# buck_module_5v.net
KiCad netlist of a schematic drawn in EAGLE
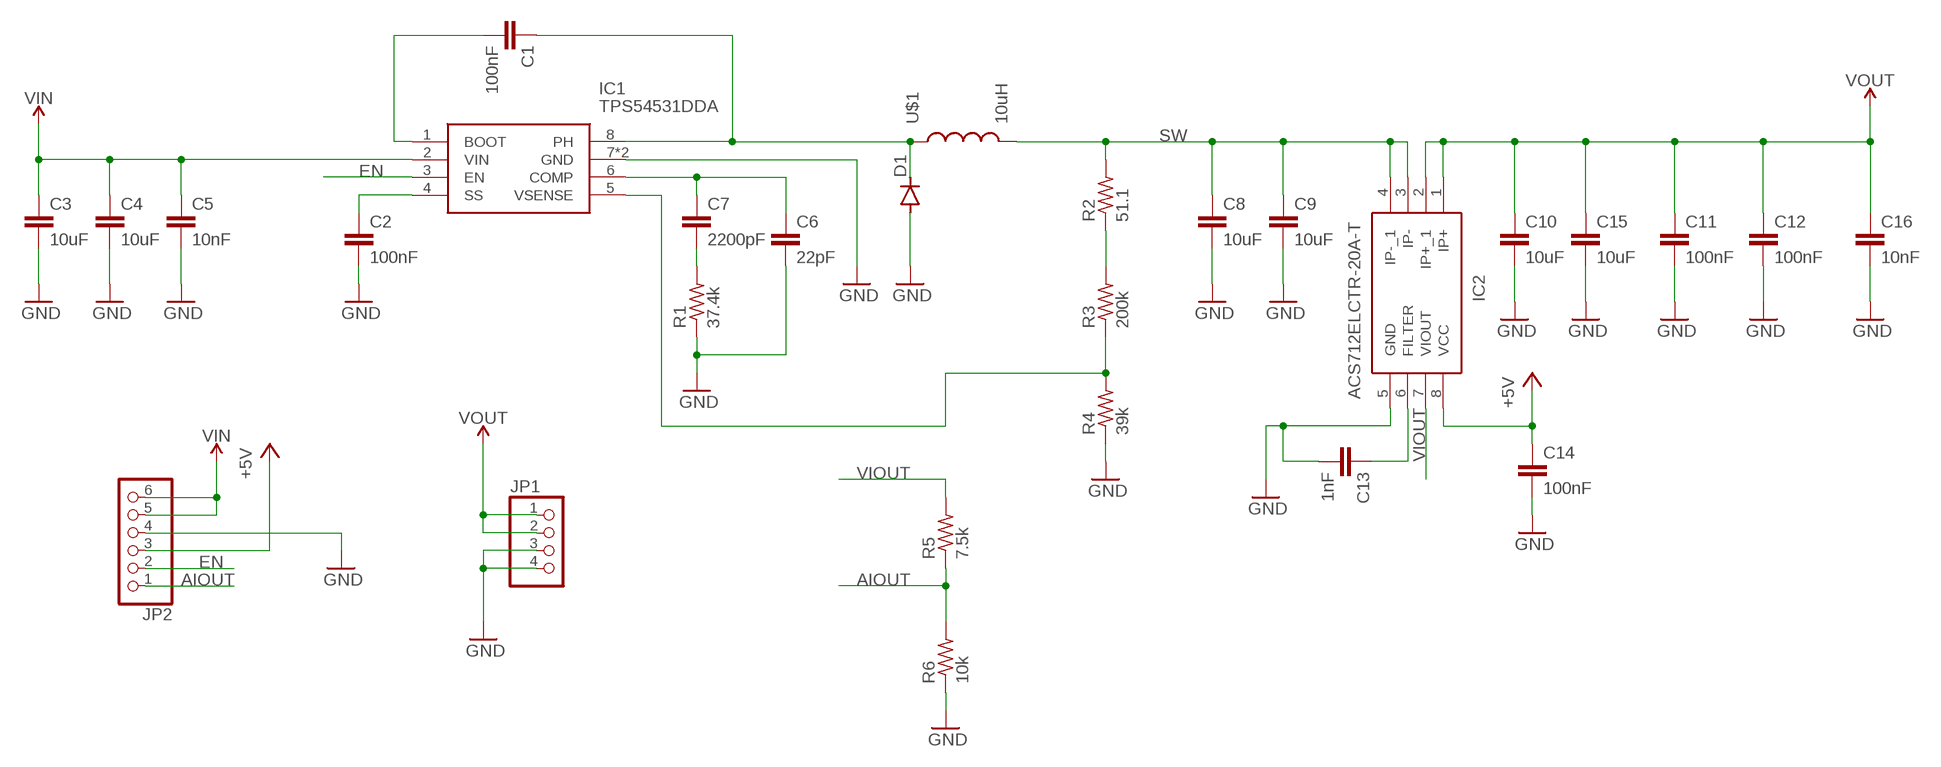
[diagram p0: schematic, sheet 1]

(export (version "E")
  (design (tool "Eeschema 10.0.6"))
  (components
    (comp (ref "C1")
      (value "100nF")
      (footprint "eagle-import:C0603")
      (libsource (lib "eagle-import") (part "C-EUC0603"))
    )
    (comp (ref "C2")
      (value "100nF")
      (footprint "eagle-import:C0603")
      (libsource (lib "eagle-import") (part "C-EUC0603"))
    )
    (comp (ref "C3")
      (value "10uF")
      (footprint "eagle-import:C1206")
      (libsource (lib "eagle-import") (part "C-EUC1206"))
    )
    (comp (ref "C4")
      (value "10uF")
      (footprint "eagle-import:C1206")
      (libsource (lib "eagle-import") (part "C-EUC1206"))
    )
    (comp (ref "C5")
      (value "10nF")
      (footprint "eagle-import:C0603")
      (libsource (lib "eagle-import") (part "C-EUC0603"))
    )
    (comp (ref "C6")
      (value "22pF")
      (footprint "eagle-import:C0603")
      (libsource (lib "eagle-import") (part "C-EUC0603"))
    )
    (comp (ref "C7")
      (value "2200pF")
      (footprint "eagle-import:C0603")
      (libsource (lib "eagle-import") (part "C-EUC0603"))
    )
    (comp (ref "C8")
      (value "10uF")
      (footprint "eagle-import:C1206")
      (libsource (lib "eagle-import") (part "C-EUC1206"))
    )
    (comp (ref "C9")
      (value "10uF")
      (footprint "eagle-import:C1206")
      (libsource (lib "eagle-import") (part "C-EUC1206"))
    )
    (comp (ref "C10")
      (value "10uF")
      (footprint "eagle-import:C1206")
      (libsource (lib "eagle-import") (part "C-EUC1206"))
    )
    (comp (ref "C11")
      (value "100nF")
      (footprint "eagle-import:C0603")
      (libsource (lib "eagle-import") (part "C-EUC0603"))
    )
    (comp (ref "C12")
      (value "100nF")
      (footprint "eagle-import:C0603")
      (libsource (lib "eagle-import") (part "C-EUC0603"))
    )
    (comp (ref "C13")
      (value "1nF")
      (footprint "eagle-import:C0603")
      (libsource (lib "eagle-import") (part "C-EUC0603"))
    )
    (comp (ref "C14")
      (value "100nF")
      (footprint "eagle-import:C0603")
      (libsource (lib "eagle-import") (part "C-EUC0603"))
    )
    (comp (ref "C15")
      (value "10uF")
      (footprint "eagle-import:C1206")
      (libsource (lib "eagle-import") (part "C-EUC1206"))
    )
    (comp (ref "C16")
      (value "10nF")
      (footprint "eagle-import:C0603")
      (libsource (lib "eagle-import") (part "C-EUC0603"))
    )
    (comp (ref "D1")
      (value "DIODE-DO214AA")
      (footprint "eagle-import:DO214AA")
      (libsource (lib "eagle-import") (part "DIODE-DO214AA"))
    )
    (comp (ref "IC1")
      (value "TPS54531DDA")
      (footprint "eagle-import:SOIC127P600X170-9N")
      (fields (field (name "MOUSER_PART_NUMBER") "595-TPS54531DDA"))
      (libsource (lib "eagle-import") (part "TPS54531DDA"))
    )
    (comp (ref "IC2")
      (value "ACS712ELCTR-20A-T")
      (footprint "eagle-import:SOIC127P600X175-8N")
      (fields (field (name "RS_PART_NUMBER") "6807135P"))
      (libsource (lib "eagle-import") (part "ACS712ELCTR-20A-T"))
    )
    (comp (ref "JP1")
      (value "PINHD-1X4")
      (footprint "eagle-import:1X04")
      (libsource (lib "eagle-import") (part "PINHD-1X4"))
    )
    (comp (ref "JP2")
      (value "PINHD-1X6")
      (footprint "eagle-import:1X06")
      (libsource (lib "eagle-import") (part "PINHD-1X6"))
    )
    (comp (ref "R1")
      (value "37.4k")
      (footprint "eagle-import:R0603")
      (libsource (lib "eagle-import") (part "R-US_R0603"))
    )
    (comp (ref "R2")
      (value "51.1")
      (footprint "eagle-import:R0603")
      (libsource (lib "eagle-import") (part "R-US_R0603"))
    )
    (comp (ref "R3")
      (value "200k")
      (footprint "eagle-import:R0603")
      (libsource (lib "eagle-import") (part "R-US_R0603"))
    )
    (comp (ref "R4")
      (value "39k")
      (footprint "eagle-import:R0603")
      (libsource (lib "eagle-import") (part "R-US_R0603"))
    )
    (comp (ref "R5")
      (value "7.5k")
      (footprint "eagle-import:R0603")
      (libsource (lib "eagle-import") (part "R-US_R0603"))
    )
    (comp (ref "R6")
      (value "10k")
      (footprint "eagle-import:R0603")
      (libsource (lib "eagle-import") (part "R-US_R0603"))
    )
    (comp (ref "U$1")
      (value "10uH")
      (footprint "eagle-import:22UH-1040-5A")
      (libsource (lib "eagle-import") (part "22UH-1040-5A"))
    )
  )
  (nets
    (net (code "1") (name "+5V") (class "Default")
      (node (ref "C14") (pin "1") (pinfunction "1_1") (pintype "passive"))
      (node (ref "IC2") (pin "8") (pinfunction "VCC_8") (pintype "power_in"))
      (node (ref "JP2") (pin "3") (pinfunction "3_3") (pintype "passive"))
    )
    (net (code "2") (name "/AIOUT") (class "Default")
      (node (ref "JP2") (pin "1") (pinfunction "1_1") (pintype "passive"))
      (node (ref "R5") (pin "1") (pinfunction "1_1") (pintype "passive"))
      (node (ref "R6") (pin "2") (pinfunction "2_2") (pintype "passive"))
    )
    (net (code "3") (name "/EN") (class "Default")
      (node (ref "IC1") (pin "3") (pinfunction "EN_3") (pintype "bidirectional"))
      (node (ref "JP2") (pin "2") (pinfunction "2_2") (pintype "passive"))
    )
    (net (code "4") (name "/SW") (class "Default")
      (node (ref "C8") (pin "1") (pinfunction "1_1") (pintype "passive"))
      (node (ref "C9") (pin "1") (pinfunction "1_1") (pintype "passive"))
      (node (ref "IC2") (pin "3") (pinfunction "IP-_3") (pintype "bidirectional"))
      (node (ref "IC2") (pin "4") (pinfunction "IP-_1_4") (pintype "bidirectional"))
      (node (ref "R2") (pin "2") (pinfunction "2_2") (pintype "passive"))
      (node (ref "U$1") (pin "P$2") (pinfunction "2_P$2") (pintype "passive"))
    )
    (net (code "5") (name "/VIOUT") (class "Default")
      (node (ref "IC2") (pin "7") (pinfunction "VIOUT_7") (pintype "bidirectional"))
      (node (ref "R5") (pin "2") (pinfunction "2_2") (pintype "passive"))
    )
    (net (code "6") (name "GND") (class "Default")
      (node (ref "C10") (pin "2") (pinfunction "2_2") (pintype "passive"))
      (node (ref "C11") (pin "2") (pinfunction "2_2") (pintype "passive"))
      (node (ref "C12") (pin "2") (pinfunction "2_2") (pintype "passive"))
      (node (ref "C13") (pin "2") (pinfunction "2_2") (pintype "passive"))
      (node (ref "C14") (pin "2") (pinfunction "2_2") (pintype "passive"))
      (node (ref "C15") (pin "2") (pinfunction "2_2") (pintype "passive"))
      (node (ref "C16") (pin "2") (pinfunction "2_2") (pintype "passive"))
      (node (ref "C2") (pin "2") (pinfunction "2_2") (pintype "passive"))
      (node (ref "C3") (pin "2") (pinfunction "2_2") (pintype "passive"))
      (node (ref "C4") (pin "2") (pinfunction "2_2") (pintype "passive"))
      (node (ref "C5") (pin "2") (pinfunction "2_2") (pintype "passive"))
      (node (ref "C6") (pin "2") (pinfunction "2_2") (pintype "passive"))
      (node (ref "C8") (pin "2") (pinfunction "2_2") (pintype "passive"))
      (node (ref "C9") (pin "2") (pinfunction "2_2") (pintype "passive"))
      (node (ref "D1") (pin "A") (pinfunction "A_A") (pintype "passive"))
      (node (ref "IC1") (pin "7") (pinfunction "GND_7") (pintype "bidirectional"))
      (node (ref "IC1") (pin "9") (pinfunction "GND_9") (pintype "bidirectional"))
      (node (ref "IC2") (pin "5") (pinfunction "GND_5") (pintype "power_in"))
      (node (ref "JP1") (pin "3") (pinfunction "3_3") (pintype "passive"))
      (node (ref "JP1") (pin "4") (pinfunction "4_4") (pintype "passive"))
      (node (ref "JP2") (pin "4") (pinfunction "4_4") (pintype "passive"))
      (node (ref "R1") (pin "1") (pinfunction "1_1") (pintype "passive"))
      (node (ref "R4") (pin "1") (pinfunction "1_1") (pintype "passive"))
      (node (ref "R6") (pin "1") (pinfunction "1_1") (pintype "passive"))
    )
    (net (code "7") (name "Net-(C7-Pad2)") (class "Default")
      (node (ref "C7") (pin "2") (pinfunction "2_2") (pintype "passive"))
      (node (ref "R1") (pin "2") (pinfunction "2_2") (pintype "passive"))
    )
    (net (code "8") (name "Net-(IC1-BOOT)") (class "Default")
      (node (ref "C1") (pin "2") (pinfunction "2_2") (pintype "passive"))
      (node (ref "IC1") (pin "1") (pinfunction "BOOT_1") (pintype "bidirectional"))
    )
    (net (code "9") (name "Net-(IC1-COMP)") (class "Default")
      (node (ref "C6") (pin "1") (pinfunction "1_1") (pintype "passive"))
      (node (ref "C7") (pin "1") (pinfunction "1_1") (pintype "passive"))
      (node (ref "IC1") (pin "6") (pinfunction "COMP_6") (pintype "bidirectional"))
    )
    (net (code "10") (name "Net-(IC1-PH)") (class "Default")
      (node (ref "C1") (pin "1") (pinfunction "1_1") (pintype "passive"))
      (node (ref "D1") (pin "C") (pinfunction "C_C") (pintype "passive"))
      (node (ref "IC1") (pin "8") (pinfunction "PH_8") (pintype "bidirectional"))
      (node (ref "U$1") (pin "P$1") (pinfunction "1_P$1") (pintype "passive"))
    )
    (net (code "11") (name "Net-(IC1-SS)") (class "Default")
      (node (ref "C2") (pin "1") (pinfunction "1_1") (pintype "passive"))
      (node (ref "IC1") (pin "4") (pinfunction "SS_4") (pintype "bidirectional"))
    )
    (net (code "12") (name "Net-(IC1-VSENSE)") (class "Default")
      (node (ref "IC1") (pin "5") (pinfunction "VSENSE_5") (pintype "bidirectional"))
      (node (ref "R3") (pin "1") (pinfunction "1_1") (pintype "passive"))
      (node (ref "R4") (pin "2") (pinfunction "2_2") (pintype "passive"))
    )
    (net (code "13") (name "Net-(IC2-FILTER)") (class "Default")
      (node (ref "C13") (pin "1") (pinfunction "1_1") (pintype "passive"))
      (node (ref "IC2") (pin "6") (pinfunction "FILTER_6") (pintype "bidirectional"))
    )
    (net (code "14") (name "Net-(R2-Pad1)") (class "Default")
      (node (ref "R2") (pin "1") (pinfunction "1_1") (pintype "passive"))
      (node (ref "R3") (pin "2") (pinfunction "2_2") (pintype "passive"))
    )
    (net (code "15") (name "VIN") (class "Default")
      (node (ref "C3") (pin "1") (pinfunction "1_1") (pintype "passive"))
      (node (ref "C4") (pin "1") (pinfunction "1_1") (pintype "passive"))
      (node (ref "C5") (pin "1") (pinfunction "1_1") (pintype "passive"))
      (node (ref "IC1") (pin "2") (pinfunction "VIN_2") (pintype "bidirectional"))
      (node (ref "JP2") (pin "5") (pinfunction "5_5") (pintype "passive"))
      (node (ref "JP2") (pin "6") (pinfunction "6_6") (pintype "passive"))
    )
    (net (code "16") (name "VOUT") (class "Default")
      (node (ref "C10") (pin "1") (pinfunction "1_1") (pintype "passive"))
      (node (ref "C11") (pin "1") (pinfunction "1_1") (pintype "passive"))
      (node (ref "C12") (pin "1") (pinfunction "1_1") (pintype "passive"))
      (node (ref "C15") (pin "1") (pinfunction "1_1") (pintype "passive"))
      (node (ref "C16") (pin "1") (pinfunction "1_1") (pintype "passive"))
      (node (ref "IC2") (pin "1") (pinfunction "IP+_1") (pintype "bidirectional"))
      (node (ref "IC2") (pin "2") (pinfunction "IP+_1_2") (pintype "bidirectional"))
      (node (ref "JP1") (pin "1") (pinfunction "1_1") (pintype "passive"))
      (node (ref "JP1") (pin "2") (pinfunction "2_2") (pintype "passive"))
    )
  )
)
